# M_L_ext_5w_switch.net
KiCad netlist of a schematic drawn in EAGLE
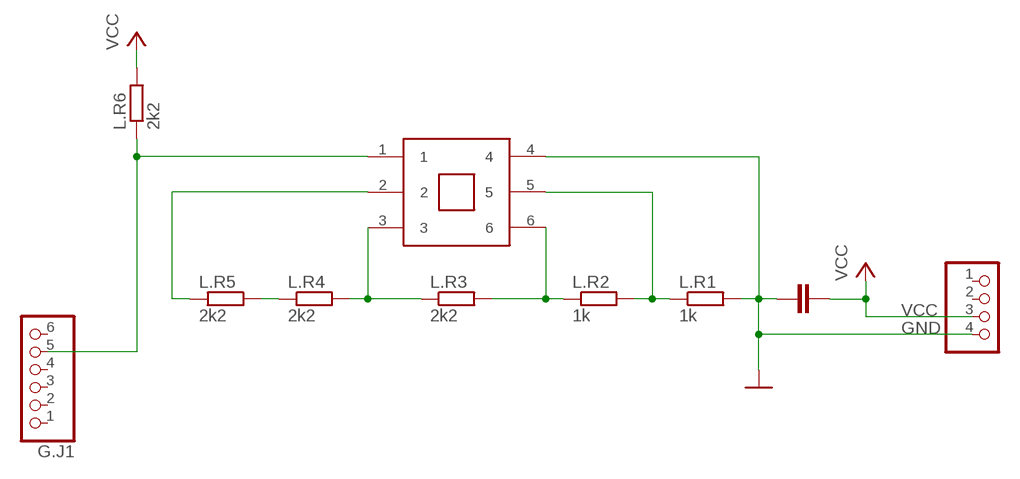
[diagram p0: schematic, sheet 1]

(export (version "E")
  (design (tool "Eeschema 10.0.6"))
  (components
    (comp (ref "G.J1")
      (value "PINHD-1X6")
      (footprint "eagle-import:1X06")
      (libsource (lib "eagle-import") (part "PINHD-1X6"))
    )
    (comp (ref "G.J2")
      (value "PINHD-1X4")
      (footprint "eagle-import:1X04")
      (libsource (lib "eagle-import") (part "PINHD-1X4"))
    )
    (comp (ref "L.C1")
      (value "100n")
      (footprint "eagle-import:C0603")
      (libsource (lib "eagle-import") (part "C-EUC0603"))
    )
    (comp (ref "L.R1")
      (value "1k")
      (footprint "eagle-import:R0603")
      (libsource (lib "eagle-import") (part "R-EU_R0603"))
    )
    (comp (ref "L.R2")
      (value "1k")
      (footprint "eagle-import:R0603")
      (libsource (lib "eagle-import") (part "R-EU_R0603"))
    )
    (comp (ref "L.R3")
      (value "2k2")
      (footprint "eagle-import:R0603")
      (libsource (lib "eagle-import") (part "R-EU_R0603"))
    )
    (comp (ref "L.R4")
      (value "2k2")
      (footprint "eagle-import:R0603")
      (libsource (lib "eagle-import") (part "R-EU_R0603"))
    )
    (comp (ref "L.R5")
      (value "2k2")
      (footprint "eagle-import:R0603")
      (libsource (lib "eagle-import") (part "R-EU_R0603"))
    )
    (comp (ref "L.R6")
      (value "2k2")
      (footprint "eagle-import:R0603")
      (libsource (lib "eagle-import") (part "R-EU_R0603"))
    )
    (comp (ref "L.SW1")
      (value "5_WAY_SWITCH")
      (footprint "eagle-import:5_WAY_SWITCH")
      (libsource (lib "eagle-import") (part "5_WAY_SWITCH"))
    )
  )
  (nets
    (net (code "1") (name "GND") (class "Default")
      (node (ref "G.J2") (pin "4") (pinfunction "4_4") (pintype "passive"))
      (node (ref "L.C1") (pin "1") (pinfunction "1_1") (pintype "passive"))
      (node (ref "L.R1") (pin "2") (pinfunction "2_2") (pintype "passive"))
      (node (ref "L.SW1") (pin "4") (pinfunction "4_4") (pintype "bidirectional"))
    )
    (net (code "2") (name "Net-(G.J1-Pad5)") (class "Default")
      (node (ref "G.J1") (pin "5") (pinfunction "5_5") (pintype "passive"))
      (node (ref "L.R6") (pin "1") (pinfunction "1_1") (pintype "passive"))
      (node (ref "L.SW1") (pin "1") (pinfunction "1_1") (pintype "bidirectional"))
    )
    (net (code "3") (name "Net-(L.R1-Pad1)") (class "Default")
      (node (ref "L.R1") (pin "1") (pinfunction "1_1") (pintype "passive"))
      (node (ref "L.R2") (pin "2") (pinfunction "2_2") (pintype "passive"))
      (node (ref "L.SW1") (pin "5") (pinfunction "5_5") (pintype "bidirectional"))
    )
    (net (code "4") (name "Net-(L.R2-Pad1)") (class "Default")
      (node (ref "L.R2") (pin "1") (pinfunction "1_1") (pintype "passive"))
      (node (ref "L.R3") (pin "2") (pinfunction "2_2") (pintype "passive"))
      (node (ref "L.SW1") (pin "6") (pinfunction "6_6") (pintype "bidirectional"))
    )
    (net (code "5") (name "Net-(L.R3-Pad1)") (class "Default")
      (node (ref "L.R3") (pin "1") (pinfunction "1_1") (pintype "passive"))
      (node (ref "L.R4") (pin "2") (pinfunction "2_2") (pintype "passive"))
      (node (ref "L.SW1") (pin "3") (pinfunction "3_3") (pintype "bidirectional"))
    )
    (net (code "6") (name "Net-(L.R4-Pad1)") (class "Default")
      (node (ref "L.R4") (pin "1") (pinfunction "1_1") (pintype "passive"))
      (node (ref "L.R5") (pin "1") (pinfunction "1_1") (pintype "passive"))
    )
    (net (code "7") (name "Net-(L.R5-Pad2)") (class "Default")
      (node (ref "L.R5") (pin "2") (pinfunction "2_2") (pintype "passive"))
      (node (ref "L.SW1") (pin "2") (pinfunction "2_2") (pintype "bidirectional"))
    )
    (net (code "8") (name "VCC") (class "Default")
      (node (ref "G.J2") (pin "3") (pinfunction "3_3") (pintype "passive"))
      (node (ref "L.C1") (pin "2") (pinfunction "2_2") (pintype "passive"))
      (node (ref "L.R6") (pin "2") (pinfunction "2_2") (pintype "passive"))
    )
    (net (code "9") (name "unconnected-(G.J1-Pad1)") (class "Default")
      (node (ref "G.J1") (pin "1") (pinfunction "1_1") (pintype "passive"))
    )
    (net (code "10") (name "unconnected-(G.J1-Pad2)") (class "Default")
      (node (ref "G.J1") (pin "2") (pinfunction "2_2") (pintype "passive"))
    )
    (net (code "11") (name "unconnected-(G.J1-Pad3)") (class "Default")
      (node (ref "G.J1") (pin "3") (pinfunction "3_3") (pintype "passive"))
    )
    (net (code "12") (name "unconnected-(G.J1-Pad4)") (class "Default")
      (node (ref "G.J1") (pin "4") (pinfunction "4_4") (pintype "passive"))
    )
    (net (code "13") (name "unconnected-(G.J1-Pad6)") (class "Default")
      (node (ref "G.J1") (pin "6") (pinfunction "6_6") (pintype "passive"))
    )
    (net (code "14") (name "unconnected-(G.J2-Pad1)") (class "Default")
      (node (ref "G.J2") (pin "1") (pinfunction "1_1") (pintype "passive"))
    )
    (net (code "15") (name "unconnected-(G.J2-Pad2)") (class "Default")
      (node (ref "G.J2") (pin "2") (pinfunction "2_2") (pintype "passive"))
    )
  )
)
